# scarab-shield.net
KiCad netlist of a schematic drawn in EAGLE
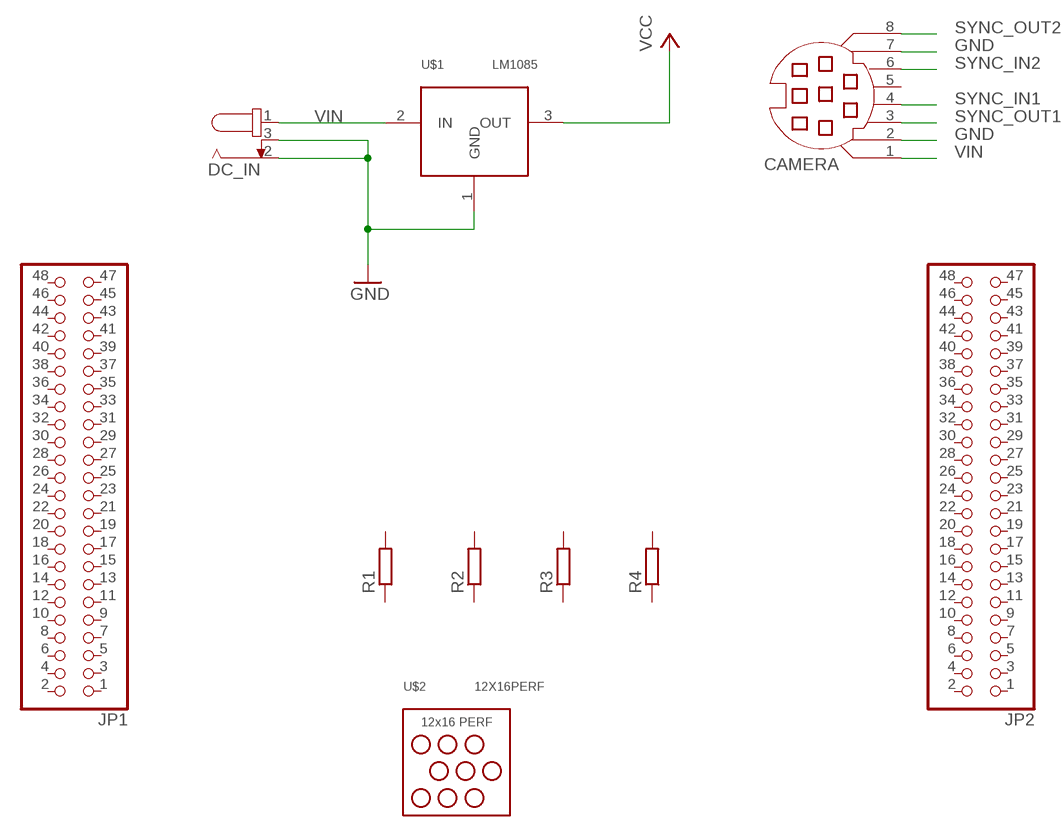
[diagram p0: schematic, sheet 1]

(export (version "E")
  (design (tool "Eeschema 10.0.6"))
  (components
    (comp (ref "CAMERA")
      (value "MD08SS")
      (footprint "eagle-import:MDIN08SS")
      (libsource (lib "eagle-import") (part "MD08SS"))
    )
    (comp (ref "DC_IN")
      (value "694106105102")
      (footprint "eagle-import:694106105102")
      (libsource (lib "eagle-import") (part "694106105102"))
    )
    (comp (ref "JP1")
      (value "PINHD-2X24")
      (footprint "eagle-import:2X24")
      (libsource (lib "eagle-import") (part "PINHD-2X24"))
    )
    (comp (ref "JP2")
      (value "PINHD-2X24")
      (footprint "eagle-import:2X24")
      (libsource (lib "eagle-import") (part "PINHD-2X24"))
    )
    (comp (ref "R1")
      (value "R-EU_M1206")
      (footprint "eagle-import:M1206")
      (libsource (lib "eagle-import") (part "R-EU_M1206"))
    )
    (comp (ref "R2")
      (value "R-EU_M1206")
      (footprint "eagle-import:M1206")
      (libsource (lib "eagle-import") (part "R-EU_M1206"))
    )
    (comp (ref "R3")
      (value "R-EU_M1206")
      (footprint "eagle-import:M1206")
      (libsource (lib "eagle-import") (part "R-EU_M1206"))
    )
    (comp (ref "R4")
      (value "R-EU_M1206")
      (footprint "eagle-import:M1206")
      (libsource (lib "eagle-import") (part "R-EU_M1206"))
    )
    (comp (ref "U$1")
      (value "LM1085")
      (footprint "eagle-import:TO263")
      (libsource (lib "eagle-import") (part "LM1085"))
    )
    (comp (ref "U$2")
      (value "12X16PERF")
      (footprint "eagle-import:PERF-GRID")
      (libsource (lib "eagle-import") (part "12X16PERF"))
    )
  )
  (nets
    (net (code "1") (name "/SYNC_IN1") (class "Default")
      (node (ref "CAMERA") (pin "4") (pinfunction "4_4") (pintype "passive"))
    )
    (net (code "2") (name "/SYNC_IN2") (class "Default")
      (node (ref "CAMERA") (pin "6") (pinfunction "6_6") (pintype "passive"))
    )
    (net (code "3") (name "/SYNC_OUT1") (class "Default")
      (node (ref "CAMERA") (pin "3") (pinfunction "3_3") (pintype "passive"))
    )
    (net (code "4") (name "/SYNC_OUT2") (class "Default")
      (node (ref "CAMERA") (pin "8") (pinfunction "8_8") (pintype "passive"))
    )
    (net (code "5") (name "/VIN") (class "Default")
      (node (ref "CAMERA") (pin "1") (pinfunction "1_1") (pintype "passive"))
      (node (ref "DC_IN") (pin "1") (pinfunction "1_1") (pintype "passive"))
      (node (ref "U$1") (pin "2") (pinfunction "IN_2") (pintype "bidirectional"))
    )
    (net (code "6") (name "GND") (class "Default")
      (node (ref "CAMERA") (pin "2") (pinfunction "2_2") (pintype "passive"))
      (node (ref "CAMERA") (pin "7") (pinfunction "7_7") (pintype "passive"))
      (node (ref "DC_IN") (pin "2") (pinfunction "2_2") (pintype "passive"))
      (node (ref "DC_IN") (pin "3") (pinfunction "3_3") (pintype "passive"))
      (node (ref "U$1") (pin "1") (pinfunction "GND_1") (pintype "bidirectional"))
    )
    (net (code "7") (name "VCC") (class "Default")
      (node (ref "U$1") (pin "3") (pinfunction "OUT_3") (pintype "bidirectional"))
    )
    (net (code "8") (name "unconnected-(CAMERA-Pad5)") (class "Default")
      (node (ref "CAMERA") (pin "5") (pinfunction "5_5") (pintype "passive"))
    )
    (net (code "9") (name "unconnected-(JP1-Pad1)") (class "Default")
      (node (ref "JP1") (pin "1") (pinfunction "1_1") (pintype "passive"))
    )
    (net (code "10") (name "unconnected-(JP1-Pad2)") (class "Default")
      (node (ref "JP1") (pin "2") (pinfunction "2_2") (pintype "passive"))
    )
    (net (code "11") (name "unconnected-(JP1-Pad3)") (class "Default")
      (node (ref "JP1") (pin "3") (pinfunction "3_3") (pintype "passive"))
    )
    (net (code "12") (name "unconnected-(JP1-Pad4)") (class "Default")
      (node (ref "JP1") (pin "4") (pinfunction "4_4") (pintype "passive"))
    )
    (net (code "13") (name "unconnected-(JP1-Pad5)") (class "Default")
      (node (ref "JP1") (pin "5") (pinfunction "5_5") (pintype "passive"))
    )
    (net (code "14") (name "unconnected-(JP1-Pad6)") (class "Default")
      (node (ref "JP1") (pin "6") (pinfunction "6_6") (pintype "passive"))
    )
    (net (code "15") (name "unconnected-(JP1-Pad7)") (class "Default")
      (node (ref "JP1") (pin "7") (pinfunction "7_7") (pintype "passive"))
    )
    (net (code "16") (name "unconnected-(JP1-Pad8)") (class "Default")
      (node (ref "JP1") (pin "8") (pinfunction "8_8") (pintype "passive"))
    )
    (net (code "17") (name "unconnected-(JP1-Pad9)") (class "Default")
      (node (ref "JP1") (pin "9") (pinfunction "9_9") (pintype "passive"))
    )
    (net (code "18") (name "unconnected-(JP1-Pad10)") (class "Default")
      (node (ref "JP1") (pin "10") (pinfunction "10_10") (pintype "passive"))
    )
    (net (code "19") (name "unconnected-(JP1-Pad11)") (class "Default")
      (node (ref "JP1") (pin "11") (pinfunction "11_11") (pintype "passive"))
    )
    (net (code "20") (name "unconnected-(JP1-Pad12)") (class "Default")
      (node (ref "JP1") (pin "12") (pinfunction "12_12") (pintype "passive"))
    )
    (net (code "21") (name "unconnected-(JP1-Pad13)") (class "Default")
      (node (ref "JP1") (pin "13") (pinfunction "13_13") (pintype "passive"))
    )
    (net (code "22") (name "unconnected-(JP1-Pad14)") (class "Default")
      (node (ref "JP1") (pin "14") (pinfunction "14_14") (pintype "passive"))
    )
    (net (code "23") (name "unconnected-(JP1-Pad15)") (class "Default")
      (node (ref "JP1") (pin "15") (pinfunction "15_15") (pintype "passive"))
    )
    (net (code "24") (name "unconnected-(JP1-Pad16)") (class "Default")
      (node (ref "JP1") (pin "16") (pinfunction "16_16") (pintype "passive"))
    )
    (net (code "25") (name "unconnected-(JP1-Pad17)") (class "Default")
      (node (ref "JP1") (pin "17") (pinfunction "17_17") (pintype "passive"))
    )
    (net (code "26") (name "unconnected-(JP1-Pad18)") (class "Default")
      (node (ref "JP1") (pin "18") (pinfunction "18_18") (pintype "passive"))
    )
    (net (code "27") (name "unconnected-(JP1-Pad19)") (class "Default")
      (node (ref "JP1") (pin "19") (pinfunction "19_19") (pintype "passive"))
    )
    (net (code "28") (name "unconnected-(JP1-Pad20)") (class "Default")
      (node (ref "JP1") (pin "20") (pinfunction "20_20") (pintype "passive"))
    )
    (net (code "29") (name "unconnected-(JP1-Pad21)") (class "Default")
      (node (ref "JP1") (pin "21") (pinfunction "21_21") (pintype "passive"))
    )
    (net (code "30") (name "unconnected-(JP1-Pad22)") (class "Default")
      (node (ref "JP1") (pin "22") (pinfunction "22_22") (pintype "passive"))
    )
    (net (code "31") (name "unconnected-(JP1-Pad23)") (class "Default")
      (node (ref "JP1") (pin "23") (pinfunction "23_23") (pintype "passive"))
    )
    (net (code "32") (name "unconnected-(JP1-Pad24)") (class "Default")
      (node (ref "JP1") (pin "24") (pinfunction "24_24") (pintype "passive"))
    )
    (net (code "33") (name "unconnected-(JP1-Pad25)") (class "Default")
      (node (ref "JP1") (pin "25") (pinfunction "25_25") (pintype "passive"))
    )
    (net (code "34") (name "unconnected-(JP1-Pad26)") (class "Default")
      (node (ref "JP1") (pin "26") (pinfunction "26_26") (pintype "passive"))
    )
    (net (code "35") (name "unconnected-(JP1-Pad27)") (class "Default")
      (node (ref "JP1") (pin "27") (pinfunction "27_27") (pintype "passive"))
    )
    (net (code "36") (name "unconnected-(JP1-Pad28)") (class "Default")
      (node (ref "JP1") (pin "28") (pinfunction "28_28") (pintype "passive"))
    )
    (net (code "37") (name "unconnected-(JP1-Pad29)") (class "Default")
      (node (ref "JP1") (pin "29") (pinfunction "29_29") (pintype "passive"))
    )
    (net (code "38") (name "unconnected-(JP1-Pad30)") (class "Default")
      (node (ref "JP1") (pin "30") (pinfunction "30_30") (pintype "passive"))
    )
    (net (code "39") (name "unconnected-(JP1-Pad31)") (class "Default")
      (node (ref "JP1") (pin "31") (pinfunction "31_31") (pintype "passive"))
    )
    (net (code "40") (name "unconnected-(JP1-Pad32)") (class "Default")
      (node (ref "JP1") (pin "32") (pinfunction "32_32") (pintype "passive"))
    )
    (net (code "41") (name "unconnected-(JP1-Pad33)") (class "Default")
      (node (ref "JP1") (pin "33") (pinfunction "33_33") (pintype "passive"))
    )
    (net (code "42") (name "unconnected-(JP1-Pad34)") (class "Default")
      (node (ref "JP1") (pin "34") (pinfunction "34_34") (pintype "passive"))
    )
    (net (code "43") (name "unconnected-(JP1-Pad35)") (class "Default")
      (node (ref "JP1") (pin "35") (pinfunction "35_35") (pintype "passive"))
    )
    (net (code "44") (name "unconnected-(JP1-Pad36)") (class "Default")
      (node (ref "JP1") (pin "36") (pinfunction "36_36") (pintype "passive"))
    )
    (net (code "45") (name "unconnected-(JP1-Pad37)") (class "Default")
      (node (ref "JP1") (pin "37") (pinfunction "37_37") (pintype "passive"))
    )
    (net (code "46") (name "unconnected-(JP1-Pad38)") (class "Default")
      (node (ref "JP1") (pin "38") (pinfunction "38_38") (pintype "passive"))
    )
    (net (code "47") (name "unconnected-(JP1-Pad39)") (class "Default")
      (node (ref "JP1") (pin "39") (pinfunction "39_39") (pintype "passive"))
    )
    (net (code "48") (name "unconnected-(JP1-Pad40)") (class "Default")
      (node (ref "JP1") (pin "40") (pinfunction "40_40") (pintype "passive"))
    )
    (net (code "49") (name "unconnected-(JP1-Pad41)") (class "Default")
      (node (ref "JP1") (pin "41") (pinfunction "41_41") (pintype "passive"))
    )
    (net (code "50") (name "unconnected-(JP1-Pad42)") (class "Default")
      (node (ref "JP1") (pin "42") (pinfunction "42_42") (pintype "passive"))
    )
    (net (code "51") (name "unconnected-(JP1-Pad43)") (class "Default")
      (node (ref "JP1") (pin "43") (pinfunction "43_43") (pintype "passive"))
    )
    (net (code "52") (name "unconnected-(JP1-Pad44)") (class "Default")
      (node (ref "JP1") (pin "44") (pinfunction "44_44") (pintype "passive"))
    )
    (net (code "53") (name "unconnected-(JP1-Pad45)") (class "Default")
      (node (ref "JP1") (pin "45") (pinfunction "45_45") (pintype "passive"))
    )
    (net (code "54") (name "unconnected-(JP1-Pad46)") (class "Default")
      (node (ref "JP1") (pin "46") (pinfunction "46_46") (pintype "passive"))
    )
    (net (code "55") (name "unconnected-(JP1-Pad47)") (class "Default")
      (node (ref "JP1") (pin "47") (pinfunction "47_47") (pintype "passive"))
    )
    (net (code "56") (name "unconnected-(JP1-Pad48)") (class "Default")
      (node (ref "JP1") (pin "48") (pinfunction "48_48") (pintype "passive"))
    )
    (net (code "57") (name "unconnected-(JP2-Pad1)") (class "Default")
      (node (ref "JP2") (pin "1") (pinfunction "1_1") (pintype "passive"))
    )
    (net (code "58") (name "unconnected-(JP2-Pad2)") (class "Default")
      (node (ref "JP2") (pin "2") (pinfunction "2_2") (pintype "passive"))
    )
    (net (code "59") (name "unconnected-(JP2-Pad3)") (class "Default")
      (node (ref "JP2") (pin "3") (pinfunction "3_3") (pintype "passive"))
    )
    (net (code "60") (name "unconnected-(JP2-Pad4)") (class "Default")
      (node (ref "JP2") (pin "4") (pinfunction "4_4") (pintype "passive"))
    )
    (net (code "61") (name "unconnected-(JP2-Pad5)") (class "Default")
      (node (ref "JP2") (pin "5") (pinfunction "5_5") (pintype "passive"))
    )
    (net (code "62") (name "unconnected-(JP2-Pad6)") (class "Default")
      (node (ref "JP2") (pin "6") (pinfunction "6_6") (pintype "passive"))
    )
    (net (code "63") (name "unconnected-(JP2-Pad7)") (class "Default")
      (node (ref "JP2") (pin "7") (pinfunction "7_7") (pintype "passive"))
    )
    (net (code "64") (name "unconnected-(JP2-Pad8)") (class "Default")
      (node (ref "JP2") (pin "8") (pinfunction "8_8") (pintype "passive"))
    )
    (net (code "65") (name "unconnected-(JP2-Pad9)") (class "Default")
      (node (ref "JP2") (pin "9") (pinfunction "9_9") (pintype "passive"))
    )
    (net (code "66") (name "unconnected-(JP2-Pad10)") (class "Default")
      (node (ref "JP2") (pin "10") (pinfunction "10_10") (pintype "passive"))
    )
    (net (code "67") (name "unconnected-(JP2-Pad11)") (class "Default")
      (node (ref "JP2") (pin "11") (pinfunction "11_11") (pintype "passive"))
    )
    (net (code "68") (name "unconnected-(JP2-Pad12)") (class "Default")
      (node (ref "JP2") (pin "12") (pinfunction "12_12") (pintype "passive"))
    )
    (net (code "69") (name "unconnected-(JP2-Pad13)") (class "Default")
      (node (ref "JP2") (pin "13") (pinfunction "13_13") (pintype "passive"))
    )
    (net (code "70") (name "unconnected-(JP2-Pad14)") (class "Default")
      (node (ref "JP2") (pin "14") (pinfunction "14_14") (pintype "passive"))
    )
    (net (code "71") (name "unconnected-(JP2-Pad15)") (class "Default")
      (node (ref "JP2") (pin "15") (pinfunction "15_15") (pintype "passive"))
    )
    (net (code "72") (name "unconnected-(JP2-Pad16)") (class "Default")
      (node (ref "JP2") (pin "16") (pinfunction "16_16") (pintype "passive"))
    )
    (net (code "73") (name "unconnected-(JP2-Pad17)") (class "Default")
      (node (ref "JP2") (pin "17") (pinfunction "17_17") (pintype "passive"))
    )
    (net (code "74") (name "unconnected-(JP2-Pad18)") (class "Default")
      (node (ref "JP2") (pin "18") (pinfunction "18_18") (pintype "passive"))
    )
    (net (code "75") (name "unconnected-(JP2-Pad19)") (class "Default")
      (node (ref "JP2") (pin "19") (pinfunction "19_19") (pintype "passive"))
    )
    (net (code "76") (name "unconnected-(JP2-Pad20)") (class "Default")
      (node (ref "JP2") (pin "20") (pinfunction "20_20") (pintype "passive"))
    )
    (net (code "77") (name "unconnected-(JP2-Pad21)") (class "Default")
      (node (ref "JP2") (pin "21") (pinfunction "21_21") (pintype "passive"))
    )
    (net (code "78") (name "unconnected-(JP2-Pad22)") (class "Default")
      (node (ref "JP2") (pin "22") (pinfunction "22_22") (pintype "passive"))
    )
    (net (code "79") (name "unconnected-(JP2-Pad23)") (class "Default")
      (node (ref "JP2") (pin "23") (pinfunction "23_23") (pintype "passive"))
    )
    (net (code "80") (name "unconnected-(JP2-Pad24)") (class "Default")
      (node (ref "JP2") (pin "24") (pinfunction "24_24") (pintype "passive"))
    )
    (net (code "81") (name "unconnected-(JP2-Pad25)") (class "Default")
      (node (ref "JP2") (pin "25") (pinfunction "25_25") (pintype "passive"))
    )
    (net (code "82") (name "unconnected-(JP2-Pad26)") (class "Default")
      (node (ref "JP2") (pin "26") (pinfunction "26_26") (pintype "passive"))
    )
    (net (code "83") (name "unconnected-(JP2-Pad27)") (class "Default")
      (node (ref "JP2") (pin "27") (pinfunction "27_27") (pintype "passive"))
    )
    (net (code "84") (name "unconnected-(JP2-Pad28)") (class "Default")
      (node (ref "JP2") (pin "28") (pinfunction "28_28") (pintype "passive"))
    )
    (net (code "85") (name "unconnected-(JP2-Pad29)") (class "Default")
      (node (ref "JP2") (pin "29") (pinfunction "29_29") (pintype "passive"))
    )
    (net (code "86") (name "unconnected-(JP2-Pad30)") (class "Default")
      (node (ref "JP2") (pin "30") (pinfunction "30_30") (pintype "passive"))
    )
    (net (code "87") (name "unconnected-(JP2-Pad31)") (class "Default")
      (node (ref "JP2") (pin "31") (pinfunction "31_31") (pintype "passive"))
    )
    (net (code "88") (name "unconnected-(JP2-Pad32)") (class "Default")
      (node (ref "JP2") (pin "32") (pinfunction "32_32") (pintype "passive"))
    )
    (net (code "89") (name "unconnected-(JP2-Pad33)") (class "Default")
      (node (ref "JP2") (pin "33") (pinfunction "33_33") (pintype "passive"))
    )
    (net (code "90") (name "unconnected-(JP2-Pad34)") (class "Default")
      (node (ref "JP2") (pin "34") (pinfunction "34_34") (pintype "passive"))
    )
    (net (code "91") (name "unconnected-(JP2-Pad35)") (class "Default")
      (node (ref "JP2") (pin "35") (pinfunction "35_35") (pintype "passive"))
    )
    (net (code "92") (name "unconnected-(JP2-Pad36)") (class "Default")
      (node (ref "JP2") (pin "36") (pinfunction "36_36") (pintype "passive"))
    )
    (net (code "93") (name "unconnected-(JP2-Pad37)") (class "Default")
      (node (ref "JP2") (pin "37") (pinfunction "37_37") (pintype "passive"))
    )
    (net (code "94") (name "unconnected-(JP2-Pad38)") (class "Default")
      (node (ref "JP2") (pin "38") (pinfunction "38_38") (pintype "passive"))
    )
    (net (code "95") (name "unconnected-(JP2-Pad39)") (class "Default")
      (node (ref "JP2") (pin "39") (pinfunction "39_39") (pintype "passive"))
    )
    (net (code "96") (name "unconnected-(JP2-Pad40)") (class "Default")
      (node (ref "JP2") (pin "40") (pinfunction "40_40") (pintype "passive"))
    )
    (net (code "97") (name "unconnected-(JP2-Pad41)") (class "Default")
      (node (ref "JP2") (pin "41") (pinfunction "41_41") (pintype "passive"))
    )
    (net (code "98") (name "unconnected-(JP2-Pad42)") (class "Default")
      (node (ref "JP2") (pin "42") (pinfunction "42_42") (pintype "passive"))
    )
    (net (code "99") (name "unconnected-(JP2-Pad43)") (class "Default")
      (node (ref "JP2") (pin "43") (pinfunction "43_43") (pintype "passive"))
    )
    (net (code "100") (name "unconnected-(JP2-Pad44)") (class "Default")
      (node (ref "JP2") (pin "44") (pinfunction "44_44") (pintype "passive"))
    )
    (net (code "101") (name "unconnected-(JP2-Pad45)") (class "Default")
      (node (ref "JP2") (pin "45") (pinfunction "45_45") (pintype "passive"))
    )
    (net (code "102") (name "unconnected-(JP2-Pad46)") (class "Default")
      (node (ref "JP2") (pin "46") (pinfunction "46_46") (pintype "passive"))
    )
    (net (code "103") (name "unconnected-(JP2-Pad47)") (class "Default")
      (node (ref "JP2") (pin "47") (pinfunction "47_47") (pintype "passive"))
    )
    (net (code "104") (name "unconnected-(JP2-Pad48)") (class "Default")
      (node (ref "JP2") (pin "48") (pinfunction "48_48") (pintype "passive"))
    )
    (net (code "105") (name "unconnected-(R1-Pad1)") (class "Default")
      (node (ref "R1") (pin "1") (pinfunction "1_1") (pintype "passive"))
    )
    (net (code "106") (name "unconnected-(R1-Pad2)") (class "Default")
      (node (ref "R1") (pin "2") (pinfunction "2_2") (pintype "passive"))
    )
    (net (code "107") (name "unconnected-(R2-Pad1)") (class "Default")
      (node (ref "R2") (pin "1") (pinfunction "1_1") (pintype "passive"))
    )
    (net (code "108") (name "unconnected-(R2-Pad2)") (class "Default")
      (node (ref "R2") (pin "2") (pinfunction "2_2") (pintype "passive"))
    )
    (net (code "109") (name "unconnected-(R3-Pad1)") (class "Default")
      (node (ref "R3") (pin "1") (pinfunction "1_1") (pintype "passive"))
    )
    (net (code "110") (name "unconnected-(R3-Pad2)") (class "Default")
      (node (ref "R3") (pin "2") (pinfunction "2_2") (pintype "passive"))
    )
    (net (code "111") (name "unconnected-(R4-Pad1)") (class "Default")
      (node (ref "R4") (pin "1") (pinfunction "1_1") (pintype "passive"))
    )
    (net (code "112") (name "unconnected-(R4-Pad2)") (class "Default")
      (node (ref "R4") (pin "2") (pinfunction "2_2") (pintype "passive"))
    )
  )
)
